# BANK0.net
KiCad netlist of a schematic drawn in Altium Designer
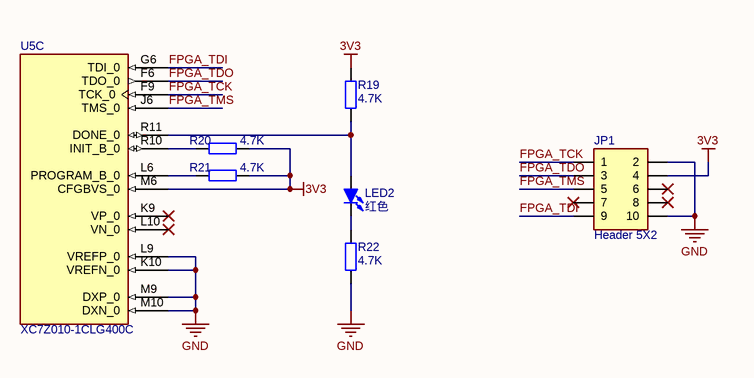
[diagram p0: BANK0.SchDoc]

(export (version "E")
  (design (tool "Eeschema 10.0.6"))
  (components
    (comp (ref "JP1")
      (value "Header 5X2")
      (footprint "IDC2.54-LI-2x5P")
      (description "5*2P接插件")
      (fields (field (name "版权归属") "源创客"))
      (libsource (lib "4.5   - 接插件-脚距2.54") (part "Header 5X2"))
    )
    (comp (ref "LED2")
      (value "红色")
      (footprint "LED 0805G")
      (description "贴片LED")
      (fields (field (name "版权归属") "源创客"))
      (libsource (lib "9.1   - LED") (part "LED-SMD"))
    )
    (comp (ref "R19")
      (value "4.7K")
      (footprint "R 0402_L")
      (description "贴片电阻")
      (fields (field (name "版权归属") "源创客"))
      (libsource (lib "3.1   - 电阻-电容-电感") (part "R"))
    )
    (comp (ref "R20")
      (value "4.7K")
      (footprint "R 0402_L")
      (description "贴片电阻")
      (fields (field (name "版权归属") "源创客"))
      (libsource (lib "3.1   - 电阻-电容-电感") (part "R"))
    )
    (comp (ref "R21")
      (value "4.7K")
      (footprint "R 0402_L")
      (description "贴片电阻")
      (fields (field (name "版权归属") "源创客"))
      (libsource (lib "3.1   - 电阻-电容-电感") (part "R"))
    )
    (comp (ref "R22")
      (value "4.7K")
      (footprint "R 0402_L")
      (description "贴片电阻")
      (fields (field (name "版权归属") "源创客"))
      (libsource (lib "3.1   - 电阻-电容-电感") (part "R"))
    )
    (comp (ref "U5")
      (value "XC7Z010-1CLG400C")
      (footprint "CLG400")
      (description "ZYNQ7000芯片")
      (libsource (lib "16.2 - Xilinx芯片") (part "XC7Z010-1CLG400C"))
    )
  )
  (nets
    (net (code "1") (name "/FPGA_TCK") (class "Default")
      (node (ref "JP1") (pin "1") (pinfunction "1_1") (pintype "passive"))
      (node (ref "U5") (pin "F9") (pinfunction "TCK_0_F9") (pintype "input"))
    )
    (net (code "2") (name "/FPGA_TDI") (class "Default")
      (node (ref "JP1") (pin "9") (pinfunction "9_9") (pintype "passive"))
      (node (ref "U5") (pin "G6") (pinfunction "TDI_0_G6") (pintype "input"))
    )
    (net (code "3") (name "/FPGA_TDO") (class "Default")
      (node (ref "JP1") (pin "3") (pinfunction "3_3") (pintype "passive"))
      (node (ref "U5") (pin "F6") (pinfunction "TDO_0_F6") (pintype "output"))
    )
    (net (code "4") (name "/FPGA_TMS") (class "Default")
      (node (ref "JP1") (pin "5") (pinfunction "5_5") (pintype "passive"))
      (node (ref "U5") (pin "J6") (pinfunction "TMS_0_J6") (pintype "input"))
    )
    (net (code "5") (name "3V3") (class "Default")
      (node (ref "JP1") (pin "4") (pinfunction "4_4") (pintype "passive"))
      (node (ref "R19") (pin "2") (pinfunction "2_2") (pintype "passive"))
      (node (ref "R20") (pin "1") (pinfunction "1_1") (pintype "passive"))
      (node (ref "R21") (pin "1") (pinfunction "1_1") (pintype "passive"))
      (node (ref "U5") (pin "M6") (pinfunction "CFGBVS_0_M6") (pintype "input"))
    )
    (net (code "6") (name "GND") (class "Default")
      (node (ref "JP1") (pin "10") (pinfunction "10_10") (pintype "passive"))
      (node (ref "JP1") (pin "2") (pinfunction "2_2") (pintype "passive"))
      (node (ref "R22") (pin "1") (pinfunction "1_1") (pintype "passive"))
      (node (ref "U5") (pin "K10") (pinfunction "VREFN_0_K10") (pintype "input"))
      (node (ref "U5") (pin "L9") (pinfunction "VREFP_0_L9") (pintype "input"))
      (node (ref "U5") (pin "M10") (pinfunction "DXN_0_M10") (pintype "input"))
      (node (ref "U5") (pin "M9") (pinfunction "DXP_0_M9") (pintype "input"))
    )
    (net (code "7") (name "Net-(LED2-A)") (class "Default")
      (node (ref "LED2") (pin "1") (pinfunction "A_1") (pintype "passive"))
      (node (ref "R19") (pin "1") (pinfunction "1_1") (pintype "passive"))
      (node (ref "U5") (pin "R11") (pinfunction "DONE_0_R11") (pintype "bidirectional"))
    )
    (net (code "8") (name "Net-(LED2-K)") (class "Default")
      (node (ref "LED2") (pin "2") (pinfunction "K_2") (pintype "passive"))
      (node (ref "R22") (pin "2") (pinfunction "2_2") (pintype "passive"))
    )
    (net (code "9") (name "Net-(U5C-INIT_B_0)") (class "Default")
      (node (ref "R20") (pin "2") (pinfunction "2_2") (pintype "passive"))
      (node (ref "U5") (pin "R10") (pinfunction "INIT_B_0_R10") (pintype "bidirectional"))
    )
    (net (code "10") (name "Net-(U5C-PROGRAM_B_0)") (class "Default")
      (node (ref "R21") (pin "2") (pinfunction "2_2") (pintype "passive"))
      (node (ref "U5") (pin "L6") (pinfunction "PROGRAM_B_0_L6") (pintype "input"))
    )
    (net (code "11") (name "unconnected-(JP1-Pad6)") (class "Default")
      (node (ref "JP1") (pin "6") (pinfunction "6_6") (pintype "passive+no_connect"))
    )
    (net (code "12") (name "unconnected-(JP1-Pad7)") (class "Default")
      (node (ref "JP1") (pin "7") (pinfunction "7_7") (pintype "passive+no_connect"))
    )
    (net (code "13") (name "unconnected-(JP1-Pad8)") (class "Default")
      (node (ref "JP1") (pin "8") (pinfunction "8_8") (pintype "passive+no_connect"))
    )
    (net (code "14") (name "unconnected-(U5C-VN_0-PadL10)") (class "Default")
      (node (ref "U5") (pin "L10") (pinfunction "VN_0_L10") (pintype "input+no_connect"))
    )
    (net (code "15") (name "unconnected-(U5C-VP_0-PadK9)") (class "Default")
      (node (ref "U5") (pin "K9") (pinfunction "VP_0_K9") (pintype "input+no_connect"))
    )
  )
)
